# WL_CON.net
KiCad netlist of a schematic drawn in Altium Designer
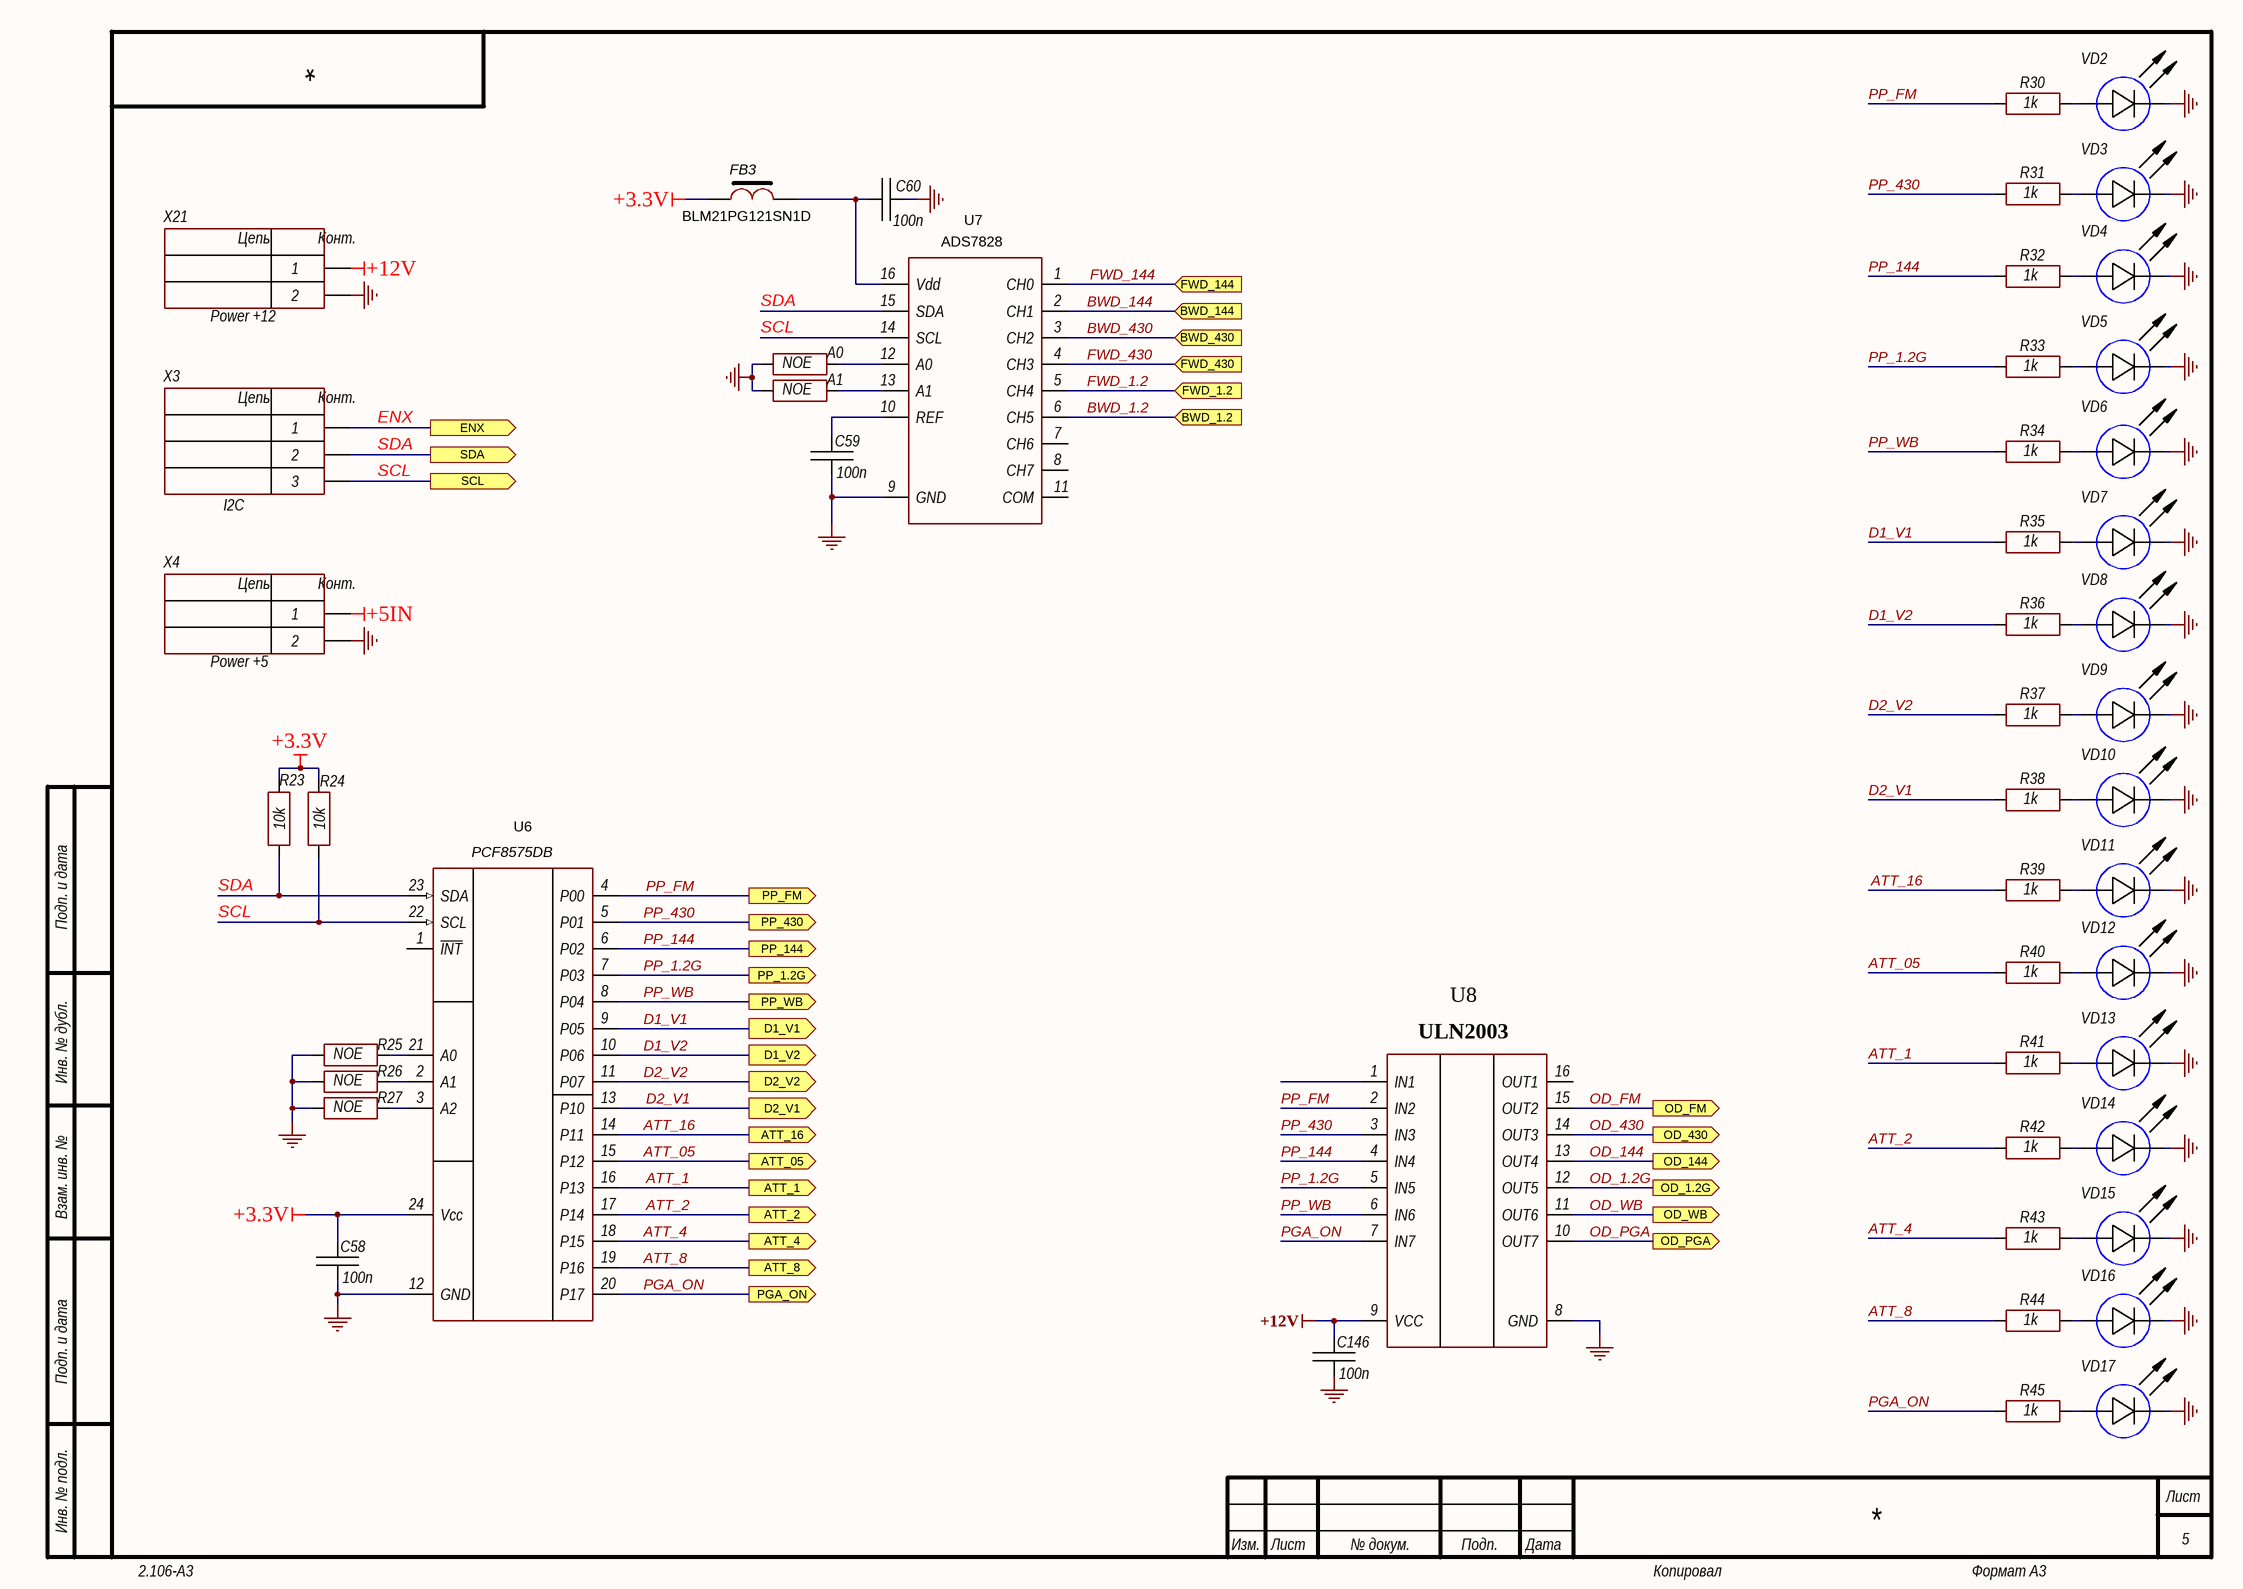
[diagram p0: WL_CON.SchDoc]

(export (version "E")
  (design (tool "Eeschema 10.0.6"))
  (components
    (comp (ref "A0")
      (value "NOE")
      (footprint "standard:CH0805R")
      (libsource (lib "Discrete") (part "Resistor"))
    )
    (comp (ref "A1")
      (value "NOE")
      (footprint "standard:CH0805R")
      (libsource (lib "Discrete") (part "Resistor"))
    )
    (comp (ref "C58")
      (value "100n")
      (footprint "standard:CH0805C")
      (libsource (lib "Discrete") (part "Capacitor"))
    )
    (comp (ref "C59")
      (value "100n")
      (footprint "standard:CH0805C")
      (libsource (lib "Discrete") (part "Capacitor"))
    )
    (comp (ref "C60")
      (value "100n")
      (footprint "standard:CH0805C")
      (libsource (lib "Discrete") (part "Capacitor"))
    )
    (comp (ref "C146")
      (value "100n")
      (footprint "standard:CH0805C")
      (libsource (lib "") (part "Capacitor_1"))
    )
    (comp (ref "FB3")
      (value "BLM21PG121SN1D")
      (footprint "CH0805L")
      (libsource (lib "Discrete") (part "FB-1"))
    )
    (comp (ref "R23") (value "10k") (footprint "standard:CH0805R") (libsource (lib "") (part "Resistor_1")))
    (comp (ref "R24") (value "10k") (footprint "standard:CH0805R") (libsource (lib "") (part "Resistor_1")))
    (comp (ref "R25")
      (value "NOE")
      (footprint "standard:CH0805R")
      (libsource (lib "Discrete") (part "Resistor"))
    )
    (comp (ref "R26")
      (value "NOE")
      (footprint "standard:CH0805R")
      (libsource (lib "Discrete") (part "Resistor"))
    )
    (comp (ref "R27")
      (value "NOE")
      (footprint "standard:CH0805R")
      (libsource (lib "Discrete") (part "Resistor"))
    )
    (comp (ref "R30")
      (value "1k")
      (footprint "standard:CH0603R")
      (libsource (lib "Discrete") (part "Resistor"))
    )
    (comp (ref "R31")
      (value "1k")
      (footprint "standard:CH0603R")
      (libsource (lib "Discrete") (part "Resistor"))
    )
    (comp (ref "R32")
      (value "1k")
      (footprint "standard:CH0603R")
      (libsource (lib "Discrete") (part "Resistor"))
    )
    (comp (ref "R33")
      (value "1k")
      (footprint "standard:CH0603R")
      (libsource (lib "Discrete") (part "Resistor"))
    )
    (comp (ref "R34")
      (value "1k")
      (footprint "standard:CH0603R")
      (libsource (lib "Discrete") (part "Resistor"))
    )
    (comp (ref "R35")
      (value "1k")
      (footprint "standard:CH0603R")
      (libsource (lib "Discrete") (part "Resistor"))
    )
    (comp (ref "R36")
      (value "1k")
      (footprint "standard:CH0603R")
      (libsource (lib "Discrete") (part "Resistor"))
    )
    (comp (ref "R37")
      (value "1k")
      (footprint "standard:CH0603R")
      (libsource (lib "Discrete") (part "Resistor"))
    )
    (comp (ref "R38")
      (value "1k")
      (footprint "standard:CH0603R")
      (libsource (lib "Discrete") (part "Resistor"))
    )
    (comp (ref "R39")
      (value "1k")
      (footprint "standard:CH0603R")
      (libsource (lib "Discrete") (part "Resistor"))
    )
    (comp (ref "R40")
      (value "1k")
      (footprint "standard:CH0603R")
      (libsource (lib "Discrete") (part "Resistor"))
    )
    (comp (ref "R41")
      (value "1k")
      (footprint "standard:CH0603R")
      (libsource (lib "Discrete") (part "Resistor"))
    )
    (comp (ref "R42")
      (value "1k")
      (footprint "standard:CH0603R")
      (libsource (lib "Discrete") (part "Resistor"))
    )
    (comp (ref "R43")
      (value "1k")
      (footprint "standard:CH0603R")
      (libsource (lib "Discrete") (part "Resistor"))
    )
    (comp (ref "R44")
      (value "1k")
      (footprint "standard:CH0603R")
      (libsource (lib "Discrete") (part "Resistor"))
    )
    (comp (ref "R45")
      (value "1k")
      (footprint "standard:CH0603R")
      (libsource (lib "Discrete") (part "Resistor"))
    )
    (comp (ref "U6")
      (value "PCF8575DB")
      (footprint "24-TSSOP_045")
      (libsource (lib "Digital") (part "PCF8575"))
    )
    (comp (ref "U7") (value "ADS7828") (footprint "16-SSOP") (libsource (lib "Digital") (part "ADS7828")))
    (comp (ref "U8") (value "ULN2003") (footprint "16-SOIC") (libsource (lib "Digital") (part "ULN2003_NEW")))
    (comp (ref "VD2") (value "*") (footprint "CH0603LB") (libsource (lib "Discrete") (part "LED")))
    (comp (ref "VD3") (value "*") (footprint "CH0603LB") (libsource (lib "Discrete") (part "LED")))
    (comp (ref "VD4") (value "*") (footprint "CH0603LB") (libsource (lib "") (part "LED_1")))
    (comp (ref "VD5") (value "*") (footprint "CH0603LB") (libsource (lib "Discrete") (part "LED")))
    (comp (ref "VD6") (value "*") (footprint "CH0603LB") (libsource (lib "Discrete") (part "LED")))
    (comp (ref "VD7") (value "*") (footprint "CH0603LB") (libsource (lib "Discrete") (part "LED")))
    (comp (ref "VD8") (value "*") (footprint "CH0603LB") (libsource (lib "Discrete") (part "LED")))
    (comp (ref "VD9") (value "*") (footprint "CH0603LB") (libsource (lib "Discrete") (part "LED")))
    (comp (ref "VD10") (value "*") (footprint "CH0603LB") (libsource (lib "Discrete") (part "LED")))
    (comp (ref "VD11") (value "*") (footprint "CH0603LB") (libsource (lib "Discrete") (part "LED")))
    (comp (ref "VD12") (value "*") (footprint "CH0603LB") (libsource (lib "Discrete") (part "LED")))
    (comp (ref "VD13") (value "*") (footprint "CH0603LB") (libsource (lib "Discrete") (part "LED")))
    (comp (ref "VD14") (value "*") (footprint "CH0603LB") (libsource (lib "Discrete") (part "LED")))
    (comp (ref "VD15") (value "*") (footprint "CH0603LB") (libsource (lib "Discrete") (part "LED")))
    (comp (ref "VD16") (value "*") (footprint "CH0603LB") (libsource (lib "Discrete") (part "LED")))
    (comp (ref "VD17") (value "*") (footprint "CH0603LB") (libsource (lib "Discrete") (part "LED")))
    (comp (ref "X3")
      (value "I2C")
      (footprint "custom:CON: CWF-3")
      (libsource (lib "Connectors") (part "3-Connector"))
    )
    (comp (ref "X4")
      (value "Power +5")
      (footprint "custom:CON: CWF-2")
      (libsource (lib "Connectors") (part "2-Connector"))
    )
    (comp (ref "X21")
      (value "Power +12")
      (footprint "WL_RFFC:CON: CWF-2")
      (libsource (lib "Connectors") (part "2-Connector"))
    )
  )
  (nets
    (net (code "1") (name "+3.3V") (class "Default")
      (node (ref "C58") (pin "2") (pinfunction "2_2") (pintype "power_in"))
      (node (ref "FB3") (pin "1") (pinfunction "1_1") (pintype "passive"))
      (node (ref "R23") (pin "1") (pinfunction "1_1") (pintype "passive"))
      (node (ref "R24") (pin "1") (pinfunction "1_1") (pintype "passive"))
      (node (ref "U6") (pin "24") (pinfunction "Vcc_24") (pintype "passive"))
    )
    (net (code "2") (name "+5IN") (class "Default")
      (node (ref "X4") (pin "1") (pinfunction "1_1") (pintype "passive"))
    )
    (net (code "3") (name "+12V") (class "Default")
      (node (ref "C146") (pin "2") (pinfunction "2_2") (pintype "power_in"))
      (node (ref "U8") (pin "9") (pinfunction "VCC_9") (pintype "passive"))
      (node (ref "X21") (pin "1") (pinfunction "1_1") (pintype "passive"))
    )
    (net (code "4") (name "/ATT_1") (class "Default")
      (node (ref "R41") (pin "1") (pinfunction "1_1") (pintype "passive"))
      (node (ref "U6") (pin "16") (pinfunction "P13_16") (pintype "passive"))
    )
    (net (code "5") (name "/ATT_2") (class "Default")
      (node (ref "R42") (pin "1") (pinfunction "1_1") (pintype "passive"))
      (node (ref "U6") (pin "17") (pinfunction "P14_17") (pintype "passive"))
    )
    (net (code "6") (name "/ATT_4") (class "Default")
      (node (ref "R43") (pin "1") (pinfunction "1_1") (pintype "passive"))
      (node (ref "U6") (pin "18") (pinfunction "P15_18") (pintype "passive"))
    )
    (net (code "7") (name "/ATT_05") (class "Default")
      (node (ref "R40") (pin "1") (pinfunction "1_1") (pintype "passive"))
      (node (ref "U6") (pin "15") (pinfunction "P12_15") (pintype "passive"))
    )
    (net (code "8") (name "/ATT_8") (class "Default")
      (node (ref "R44") (pin "1") (pinfunction "1_1") (pintype "passive"))
      (node (ref "U6") (pin "19") (pinfunction "P16_19") (pintype "passive"))
    )
    (net (code "9") (name "/ATT_16") (class "Default")
      (node (ref "R39") (pin "1") (pinfunction "1_1") (pintype "passive"))
      (node (ref "U6") (pin "14") (pinfunction "P11_14") (pintype "passive"))
    )
    (net (code "10") (name "/BWD_1.2") (class "Default")
      (node (ref "U7") (pin "6") (pinfunction "CH5_6") (pintype "passive"))
    )
    (net (code "11") (name "/BWD_144") (class "Default")
      (node (ref "U7") (pin "2") (pinfunction "CH1_2") (pintype "passive"))
    )
    (net (code "12") (name "/BWD_430") (class "Default")
      (node (ref "U7") (pin "3") (pinfunction "CH2_3") (pintype "passive"))
    )
    (net (code "13") (name "/D1_V1") (class "Default")
      (node (ref "R35") (pin "1") (pinfunction "1_1") (pintype "passive"))
      (node (ref "U6") (pin "9") (pinfunction "P05_9") (pintype "passive"))
    )
    (net (code "14") (name "/D1_V2") (class "Default")
      (node (ref "R36") (pin "1") (pinfunction "1_1") (pintype "passive"))
      (node (ref "U6") (pin "10") (pinfunction "P06_10") (pintype "passive"))
    )
    (net (code "15") (name "/D2_V1") (class "Default")
      (node (ref "R38") (pin "1") (pinfunction "1_1") (pintype "passive"))
      (node (ref "U6") (pin "13") (pinfunction "P10_13") (pintype "passive"))
    )
    (net (code "16") (name "/D2_V2") (class "Default")
      (node (ref "R37") (pin "1") (pinfunction "1_1") (pintype "passive"))
      (node (ref "U6") (pin "11") (pinfunction "P07_11") (pintype "passive"))
    )
    (net (code "17") (name "/ENX") (class "Default")
      (node (ref "X3") (pin "1") (pinfunction "1_1") (pintype "passive"))
    )
    (net (code "18") (name "/FWD_1.2") (class "Default")
      (node (ref "U7") (pin "5") (pinfunction "CH4_5") (pintype "passive"))
    )
    (net (code "19") (name "/FWD_144") (class "Default")
      (node (ref "U7") (pin "1") (pinfunction "CH0_1") (pintype "passive"))
    )
    (net (code "20") (name "/FWD_430") (class "Default")
      (node (ref "U7") (pin "4") (pinfunction "CH3_4") (pintype "passive"))
    )
    (net (code "21") (name "/OD_1.2G") (class "Default")
      (node (ref "U8") (pin "12") (pinfunction "OUT5_12") (pintype "passive"))
    )
    (net (code "22") (name "/OD_144") (class "Default")
      (node (ref "U8") (pin "13") (pinfunction "OUT4_13") (pintype "passive"))
    )
    (net (code "23") (name "/OD_430") (class "Default")
      (node (ref "U8") (pin "14") (pinfunction "OUT3_14") (pintype "passive"))
    )
    (net (code "24") (name "/OD_FM") (class "Default")
      (node (ref "U8") (pin "15") (pinfunction "OUT2_15") (pintype "passive"))
    )
    (net (code "25") (name "/OD_PGA") (class "Default")
      (node (ref "U8") (pin "10") (pinfunction "OUT7_10") (pintype "passive"))
    )
    (net (code "26") (name "/OD_WB") (class "Default")
      (node (ref "U8") (pin "11") (pinfunction "OUT6_11") (pintype "passive"))
    )
    (net (code "27") (name "/PGA_ON") (class "Default")
      (node (ref "R45") (pin "1") (pinfunction "1_1") (pintype "passive"))
      (node (ref "U6") (pin "20") (pinfunction "P17_20") (pintype "passive"))
      (node (ref "U8") (pin "7") (pinfunction "IN7_7") (pintype "passive"))
    )
    (net (code "28") (name "/PP_1.2G") (class "Default")
      (node (ref "R33") (pin "1") (pinfunction "1_1") (pintype "passive"))
      (node (ref "U6") (pin "7") (pinfunction "P03_7") (pintype "passive"))
      (node (ref "U8") (pin "5") (pinfunction "IN5_5") (pintype "passive"))
    )
    (net (code "29") (name "/PP_144") (class "Default")
      (node (ref "R32") (pin "1") (pinfunction "1_1") (pintype "passive"))
      (node (ref "U6") (pin "6") (pinfunction "P02_6") (pintype "passive"))
      (node (ref "U8") (pin "4") (pinfunction "IN4_4") (pintype "passive"))
    )
    (net (code "30") (name "/PP_430") (class "Default")
      (node (ref "R31") (pin "1") (pinfunction "1_1") (pintype "passive"))
      (node (ref "U6") (pin "5") (pinfunction "P01_5") (pintype "passive"))
      (node (ref "U8") (pin "3") (pinfunction "IN3_3") (pintype "passive"))
    )
    (net (code "31") (name "/PP_FM") (class "Default")
      (node (ref "R30") (pin "1") (pinfunction "1_1") (pintype "passive"))
      (node (ref "U6") (pin "4") (pinfunction "P00_4") (pintype "passive"))
      (node (ref "U8") (pin "2") (pinfunction "IN2_2") (pintype "passive"))
    )
    (net (code "32") (name "/PP_WB") (class "Default")
      (node (ref "R34") (pin "1") (pinfunction "1_1") (pintype "passive"))
      (node (ref "U6") (pin "8") (pinfunction "P04_8") (pintype "passive"))
      (node (ref "U8") (pin "6") (pinfunction "IN6_6") (pintype "passive"))
    )
    (net (code "33") (name "/SCL") (class "Default")
      (node (ref "R24") (pin "2") (pinfunction "2_2") (pintype "passive"))
      (node (ref "U6") (pin "22") (pinfunction "SCL_22") (pintype "input"))
      (node (ref "U7") (pin "14") (pinfunction "SCL_14") (pintype "passive"))
      (node (ref "X3") (pin "3") (pinfunction "3_3") (pintype "power_in"))
    )
    (net (code "34") (name "/SDA") (class "Default")
      (node (ref "R23") (pin "2") (pinfunction "2_2") (pintype "passive"))
      (node (ref "U6") (pin "23") (pinfunction "SDA_23") (pintype "input"))
      (node (ref "U7") (pin "15") (pinfunction "SDA_15") (pintype "passive"))
      (node (ref "X3") (pin "2") (pinfunction "2_2") (pintype "passive"))
    )
    (net (code "35") (name "GND") (class "Default")
      (node (ref "A0") (pin "1") (pinfunction "1_1") (pintype "passive"))
      (node (ref "A1") (pin "1") (pinfunction "1_1") (pintype "passive"))
      (node (ref "C146") (pin "1") (pinfunction "1_1") (pintype "power_in"))
      (node (ref "C58") (pin "1") (pinfunction "1_1") (pintype "power_in"))
      (node (ref "C59") (pin "1") (pinfunction "1_1") (pintype "power_in"))
      (node (ref "C60") (pin "1") (pinfunction "1_1") (pintype "power_in"))
      (node (ref "R25") (pin "1") (pinfunction "1_1") (pintype "passive"))
      (node (ref "R26") (pin "1") (pinfunction "1_1") (pintype "passive"))
      (node (ref "R27") (pin "1") (pinfunction "1_1") (pintype "passive"))
      (node (ref "U6") (pin "12") (pinfunction "GND_12") (pintype "passive"))
      (node (ref "U7") (pin "9") (pinfunction "GND_9") (pintype "passive"))
      (node (ref "U8") (pin "8") (pinfunction "GND_8") (pintype "passive"))
      (node (ref "VD10") (pin "2") (pinfunction "C_2") (pintype "passive"))
      (node (ref "VD11") (pin "2") (pinfunction "C_2") (pintype "passive"))
      (node (ref "VD12") (pin "2") (pinfunction "C_2") (pintype "passive"))
      (node (ref "VD13") (pin "2") (pinfunction "C_2") (pintype "passive"))
      (node (ref "VD14") (pin "2") (pinfunction "C_2") (pintype "passive"))
      (node (ref "VD15") (pin "2") (pinfunction "C_2") (pintype "passive"))
      (node (ref "VD16") (pin "2") (pinfunction "C_2") (pintype "passive"))
      (node (ref "VD17") (pin "2") (pinfunction "C_2") (pintype "passive"))
      (node (ref "VD2") (pin "2") (pinfunction "C_2") (pintype "passive"))
      (node (ref "VD3") (pin "2") (pinfunction "C_2") (pintype "passive"))
      (node (ref "VD4") (pin "2") (pinfunction "C_2") (pintype "passive"))
      (node (ref "VD5") (pin "2") (pinfunction "C_2") (pintype "passive"))
      (node (ref "VD6") (pin "2") (pinfunction "C_2") (pintype "passive"))
      (node (ref "VD7") (pin "2") (pinfunction "C_2") (pintype "passive"))
      (node (ref "VD8") (pin "2") (pinfunction "C_2") (pintype "passive"))
      (node (ref "VD9") (pin "2") (pinfunction "C_2") (pintype "passive"))
      (node (ref "X21") (pin "2") (pinfunction "2_2") (pintype "passive"))
      (node (ref "X4") (pin "2") (pinfunction "2_2") (pintype "passive"))
    )
    (net (code "36") (name "Net-(U6-A0)") (class "Default")
      (node (ref "R25") (pin "2") (pinfunction "2_2") (pintype "passive"))
      (node (ref "U6") (pin "21") (pinfunction "A0_21") (pintype "passive"))
    )
    (net (code "37") (name "Net-(U6-A1)") (class "Default")
      (node (ref "R26") (pin "2") (pinfunction "2_2") (pintype "passive"))
      (node (ref "U6") (pin "2") (pinfunction "A1_2") (pintype "passive"))
    )
    (net (code "38") (name "Net-(U6-A2)") (class "Default")
      (node (ref "R27") (pin "2") (pinfunction "2_2") (pintype "passive"))
      (node (ref "U6") (pin "3") (pinfunction "A2_3") (pintype "passive"))
    )
    (net (code "39") (name "Net-(U7-A0)") (class "Default")
      (node (ref "A0") (pin "2") (pinfunction "2_2") (pintype "passive"))
      (node (ref "U7") (pin "12") (pinfunction "A0_12") (pintype "passive"))
    )
    (net (code "40") (name "Net-(U7-A1)") (class "Default")
      (node (ref "A1") (pin "2") (pinfunction "2_2") (pintype "passive"))
      (node (ref "U7") (pin "13") (pinfunction "A1_13") (pintype "passive"))
    )
    (net (code "41") (name "Net-(U7-REF)") (class "Default")
      (node (ref "C59") (pin "2") (pinfunction "2_2") (pintype "power_in"))
      (node (ref "U7") (pin "10") (pinfunction "REF_10") (pintype "passive"))
    )
    (net (code "42") (name "Net-(U7-Vdd)") (class "Default")
      (node (ref "C60") (pin "2") (pinfunction "2_2") (pintype "power_in"))
      (node (ref "FB3") (pin "2") (pinfunction "2_2") (pintype "passive"))
      (node (ref "U7") (pin "16") (pinfunction "Vdd_16") (pintype "passive"))
    )
    (net (code "43") (name "Net-(VD2-A)") (class "Default")
      (node (ref "R30") (pin "2") (pinfunction "2_2") (pintype "passive"))
      (node (ref "VD2") (pin "1") (pinfunction "A_1") (pintype "passive"))
    )
    (net (code "44") (name "Net-(VD3-A)") (class "Default")
      (node (ref "R31") (pin "2") (pinfunction "2_2") (pintype "passive"))
      (node (ref "VD3") (pin "1") (pinfunction "A_1") (pintype "passive"))
    )
    (net (code "45") (name "Net-(VD4-A)") (class "Default")
      (node (ref "R32") (pin "2") (pinfunction "2_2") (pintype "passive"))
      (node (ref "VD4") (pin "1") (pinfunction "A_1") (pintype "passive"))
    )
    (net (code "46") (name "Net-(VD5-A)") (class "Default")
      (node (ref "R33") (pin "2") (pinfunction "2_2") (pintype "passive"))
      (node (ref "VD5") (pin "1") (pinfunction "A_1") (pintype "passive"))
    )
    (net (code "47") (name "Net-(VD6-A)") (class "Default")
      (node (ref "R34") (pin "2") (pinfunction "2_2") (pintype "passive"))
      (node (ref "VD6") (pin "1") (pinfunction "A_1") (pintype "passive"))
    )
    (net (code "48") (name "Net-(VD7-A)") (class "Default")
      (node (ref "R35") (pin "2") (pinfunction "2_2") (pintype "passive"))
      (node (ref "VD7") (pin "1") (pinfunction "A_1") (pintype "passive"))
    )
    (net (code "49") (name "Net-(VD8-A)") (class "Default")
      (node (ref "R36") (pin "2") (pinfunction "2_2") (pintype "passive"))
      (node (ref "VD8") (pin "1") (pinfunction "A_1") (pintype "passive"))
    )
    (net (code "50") (name "Net-(VD9-A)") (class "Default")
      (node (ref "R37") (pin "2") (pinfunction "2_2") (pintype "passive"))
      (node (ref "VD9") (pin "1") (pinfunction "A_1") (pintype "passive"))
    )
    (net (code "51") (name "Net-(VD10-A)") (class "Default")
      (node (ref "R38") (pin "2") (pinfunction "2_2") (pintype "passive"))
      (node (ref "VD10") (pin "1") (pinfunction "A_1") (pintype "passive"))
    )
    (net (code "52") (name "Net-(VD11-A)") (class "Default")
      (node (ref "R39") (pin "2") (pinfunction "2_2") (pintype "passive"))
      (node (ref "VD11") (pin "1") (pinfunction "A_1") (pintype "passive"))
    )
    (net (code "53") (name "Net-(VD12-A)") (class "Default")
      (node (ref "R40") (pin "2") (pinfunction "2_2") (pintype "passive"))
      (node (ref "VD12") (pin "1") (pinfunction "A_1") (pintype "passive"))
    )
    (net (code "54") (name "Net-(VD13-A)") (class "Default")
      (node (ref "R41") (pin "2") (pinfunction "2_2") (pintype "passive"))
      (node (ref "VD13") (pin "1") (pinfunction "A_1") (pintype "passive"))
    )
    (net (code "55") (name "Net-(VD14-A)") (class "Default")
      (node (ref "R42") (pin "2") (pinfunction "2_2") (pintype "passive"))
      (node (ref "VD14") (pin "1") (pinfunction "A_1") (pintype "passive"))
    )
    (net (code "56") (name "Net-(VD15-A)") (class "Default")
      (node (ref "R43") (pin "2") (pinfunction "2_2") (pintype "passive"))
      (node (ref "VD15") (pin "1") (pinfunction "A_1") (pintype "passive"))
    )
    (net (code "57") (name "Net-(VD16-A)") (class "Default")
      (node (ref "R44") (pin "2") (pinfunction "2_2") (pintype "passive"))
      (node (ref "VD16") (pin "1") (pinfunction "A_1") (pintype "passive"))
    )
    (net (code "58") (name "Net-(VD17-A)") (class "Default")
      (node (ref "R45") (pin "2") (pinfunction "2_2") (pintype "passive"))
      (node (ref "VD17") (pin "1") (pinfunction "A_1") (pintype "passive"))
    )
    (net (code "59") (name "unconnected-(U6-~{INT}-Pad1)") (class "Default")
      (node (ref "U6") (pin "1") (pinfunction "~{INT}_1") (pintype "passive"))
    )
    (net (code "60") (name "unconnected-(U7-CH6-Pad7)") (class "Default")
      (node (ref "U7") (pin "7") (pinfunction "CH6_7") (pintype "passive"))
    )
    (net (code "61") (name "unconnected-(U7-CH7-Pad8)") (class "Default")
      (node (ref "U7") (pin "8") (pinfunction "CH7_8") (pintype "passive"))
    )
    (net (code "62") (name "unconnected-(U7-COM-Pad11)") (class "Default")
      (node (ref "U7") (pin "11") (pinfunction "COM_11") (pintype "passive"))
    )
    (net (code "63") (name "unconnected-(U8-IN1-Pad1)") (class "Default")
      (node (ref "U8") (pin "1") (pinfunction "IN1_1") (pintype "passive"))
    )
    (net (code "64") (name "unconnected-(U8-OUT1-Pad16)") (class "Default")
      (node (ref "U8") (pin "16") (pinfunction "OUT1_16") (pintype "passive"))
    )
  )
)
